# RS232_NPN_PNP_Reset.net
KiCad netlist of a schematic drawn in EAGLE
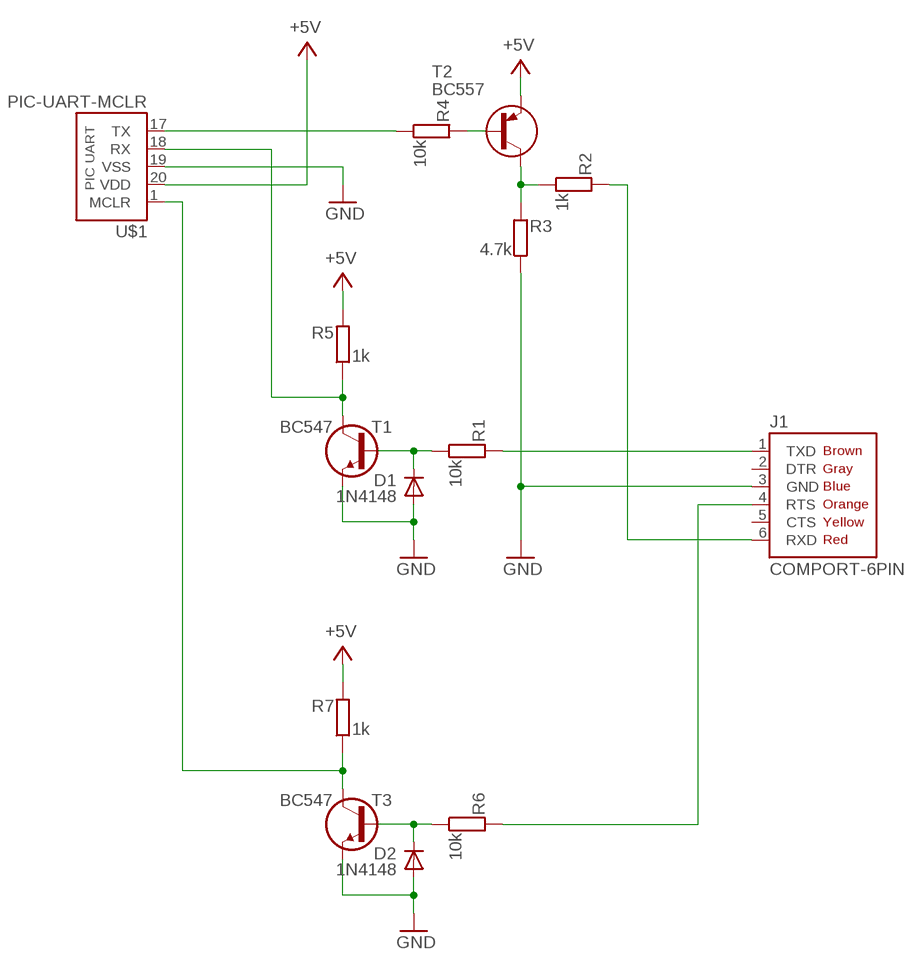
[diagram p0: schematic, sheet 1]

(export (version "E")
  (design (tool "Eeschema 10.0.6"))
  (components
    (comp (ref "D1")
      (value "1N4148")
      (footprint "eagle-import:DO34-5")
      (libsource (lib "eagle-import") (part "1N414834-5"))
    )
    (comp (ref "D2")
      (value "1N4148")
      (footprint "eagle-import:DO34-5")
      (libsource (lib "eagle-import") (part "1N414834-5"))
    )
    (comp (ref "J1")
      (value "COMPORT-6PIN")
      (footprint "eagle-import:RS232-6PIN")
      (libsource (lib "eagle-import") (part "COMPORT-6PIN"))
    )
    (comp (ref "R1")
      (value "10k")
      (footprint "eagle-import:0202_5")
      (libsource (lib "eagle-import") (part "R0202/5"))
    )
    (comp (ref "R2")
      (value "1k")
      (footprint "eagle-import:0202_5")
      (libsource (lib "eagle-import") (part "R0202/5"))
    )
    (comp (ref "R3")
      (value "4.7k")
      (footprint "eagle-import:0202_5")
      (libsource (lib "eagle-import") (part "R0202/5"))
    )
    (comp (ref "R4")
      (value "10k")
      (footprint "eagle-import:0202_5")
      (libsource (lib "eagle-import") (part "R0202/5"))
    )
    (comp (ref "R5")
      (value "1k")
      (footprint "eagle-import:0202_5")
      (libsource (lib "eagle-import") (part "R0202/5"))
    )
    (comp (ref "R6")
      (value "10k")
      (footprint "eagle-import:0202_5")
      (libsource (lib "eagle-import") (part "R0202/5"))
    )
    (comp (ref "R7")
      (value "1k")
      (footprint "eagle-import:0202_2V")
      (libsource (lib "eagle-import") (part "R0202/2V"))
    )
    (comp (ref "T1")
      (value "BC547")
      (footprint "eagle-import:TO92-CBE")
      (libsource (lib "eagle-import") (part "BC547CBE"))
    )
    (comp (ref "T2")
      (value "BC557")
      (footprint "eagle-import:TO92-CBE")
      (libsource (lib "eagle-import") (part "BC557CBE"))
    )
    (comp (ref "T3")
      (value "BC547")
      (footprint "eagle-import:TO92-CBE")
      (libsource (lib "eagle-import") (part "BC547CBE"))
    )
    (comp (ref "U$1")
      (value "PIC-UART-MCLR")
      (footprint "eagle-import:PIC-UART-MCLR")
      (libsource (lib "eagle-import") (part "PIC-UART-MCLR"))
    )
  )
  (nets
    (net (code "1") (name "+5V") (class "Default")
      (node (ref "R5") (pin "2") (pinfunction "2_2") (pintype "passive"))
      (node (ref "R7") (pin "2") (pinfunction "2_2") (pintype "passive"))
      (node (ref "T2") (pin "E") (pinfunction "E_E") (pintype "passive"))
      (node (ref "U$1") (pin "20") (pinfunction "VDD_20") (pintype "passive"))
    )
    (net (code "2") (name "GND") (class "Default")
      (node (ref "D1") (pin "A") (pinfunction "A_A") (pintype "passive"))
      (node (ref "D2") (pin "A") (pinfunction "A_A") (pintype "passive"))
      (node (ref "J1") (pin "3") (pinfunction "GND_3") (pintype "passive"))
      (node (ref "R3") (pin "1") (pinfunction "1_1") (pintype "passive"))
      (node (ref "T1") (pin "E") (pinfunction "E_E") (pintype "passive"))
      (node (ref "T3") (pin "E") (pinfunction "E_E") (pintype "passive"))
      (node (ref "U$1") (pin "19") (pinfunction "VSS_19") (pintype "passive"))
    )
    (net (code "3") (name "Net-(D1-PadC)") (class "Default")
      (node (ref "D1") (pin "C") (pinfunction "C_C") (pintype "passive"))
      (node (ref "R1") (pin "1") (pinfunction "1_1") (pintype "passive"))
      (node (ref "T1") (pin "B") (pinfunction "B_B") (pintype "passive"))
    )
    (net (code "4") (name "Net-(D2-PadC)") (class "Default")
      (node (ref "D2") (pin "C") (pinfunction "C_C") (pintype "passive"))
      (node (ref "R6") (pin "1") (pinfunction "1_1") (pintype "passive"))
      (node (ref "T3") (pin "B") (pinfunction "B_B") (pintype "passive"))
    )
    (net (code "5") (name "Net-(J1-RTS)") (class "Default")
      (node (ref "J1") (pin "4") (pinfunction "RTS_4") (pintype "passive"))
      (node (ref "R6") (pin "2") (pinfunction "2_2") (pintype "passive"))
    )
    (net (code "6") (name "Net-(J1-RXD)") (class "Default")
      (node (ref "J1") (pin "6") (pinfunction "RXD_6") (pintype "passive"))
      (node (ref "R2") (pin "2") (pinfunction "2_2") (pintype "passive"))
    )
    (net (code "7") (name "Net-(J1-TXD)") (class "Default")
      (node (ref "J1") (pin "1") (pinfunction "TXD_1") (pintype "passive"))
      (node (ref "R1") (pin "2") (pinfunction "2_2") (pintype "passive"))
    )
    (net (code "8") (name "Net-(R2-Pad1)") (class "Default")
      (node (ref "R2") (pin "1") (pinfunction "1_1") (pintype "passive"))
      (node (ref "R3") (pin "2") (pinfunction "2_2") (pintype "passive"))
      (node (ref "T2") (pin "C") (pinfunction "C_C") (pintype "passive"))
    )
    (net (code "9") (name "Net-(R4-Pad2)") (class "Default")
      (node (ref "R4") (pin "2") (pinfunction "2_2") (pintype "passive"))
      (node (ref "T2") (pin "B") (pinfunction "B_B") (pintype "passive"))
    )
    (net (code "10") (name "Net-(U$1-MCLR)") (class "Default")
      (node (ref "R7") (pin "1") (pinfunction "1_1") (pintype "passive"))
      (node (ref "T3") (pin "C") (pinfunction "C_C") (pintype "passive"))
      (node (ref "U$1") (pin "1") (pinfunction "MCLR_1") (pintype "passive"))
    )
    (net (code "11") (name "Net-(U$1-RX)") (class "Default")
      (node (ref "R5") (pin "1") (pinfunction "1_1") (pintype "passive"))
      (node (ref "T1") (pin "C") (pinfunction "C_C") (pintype "passive"))
      (node (ref "U$1") (pin "18") (pinfunction "RX_18") (pintype "passive"))
    )
    (net (code "12") (name "Net-(U$1-TX)") (class "Default")
      (node (ref "R4") (pin "1") (pinfunction "1_1") (pintype "passive"))
      (node (ref "U$1") (pin "17") (pinfunction "TX_17") (pintype "passive"))
    )
    (net (code "13") (name "unconnected-(J1-CTS-Pad5)") (class "Default")
      (node (ref "J1") (pin "5") (pinfunction "CTS_5") (pintype "passive"))
    )
    (net (code "14") (name "unconnected-(J1-DTR-Pad2)") (class "Default")
      (node (ref "J1") (pin "2") (pinfunction "DTR_2") (pintype "passive"))
    )
  )
)
